# Supply_3V3.net
KiCad netlist of a schematic drawn in Altium Designer
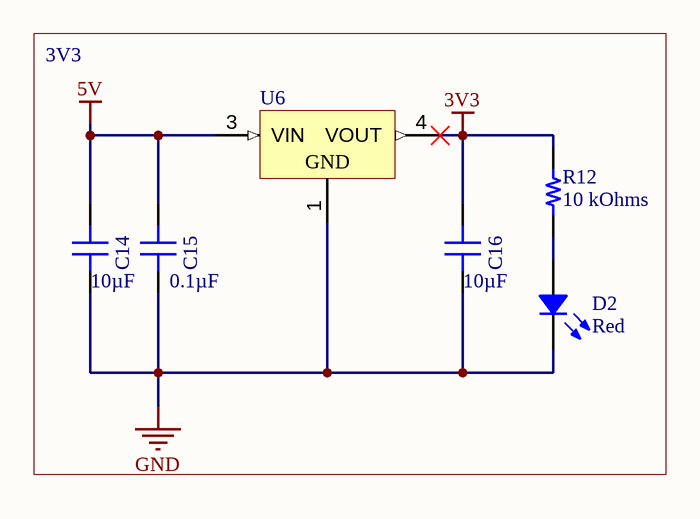
[diagram p0: Supply_3V3.SchDoc]

(export (version "E")
  (design (tool "Eeschema 10.0.6"))
  (components
    (comp (ref "C14")
      (value "10µF")
      (footprint "CAP 0805_2012")
      (description "CAP CER 10UF 16V X5R 0805")
      (fields (field (name "TOLERANCE") "±10%") (field (name "PART NUMBER") "0805YD106KAT2A"))
      (libsource (lib "Celestial Altium Library - altium_library") (part "Capacitor"))
    )
    (comp (ref "C15")
      (value "~")
      (footprint "CAP 0805_2012")
      (description "CAP CER 0.1UF 25V Z5U 0805")
      (fields
        (field (name "TOLERANCE") "-20%, +80%")
        (field (name "PART NUMBER") "08053E104ZAT2A")
        (field (name "CAPACITANCE") "0.1µF")
      )
      (libsource (lib "Celestial Altium Library - altium_library") (part "Capacitor"))
    )
    (comp (ref "C16")
      (value "10µF")
      (footprint "CAP 0805_2012")
      (description "CAP CER 10UF 16V X5R 0805")
      (fields (field (name "TOLERANCE") "±10%") (field (name "PART NUMBER") "0805YD106KAT2A"))
      (libsource (lib "Celestial Altium Library - altium_library") (part "Capacitor"))
    )
    (comp (ref "D2")
      (value "Red")
      (footprint "LED 0603_1608 RED")
      (description "LED RED CLEAR 0603 SMD")
      (fields
        (field (name "PART NUMBER") "LR Q976.01-P2R2-1")
        (field (name "MANUFACTURER") "ams-OSRAM USA Inc.")
      )
      (libsource (lib "Celestial Altium Library - altium_library") (part "LED"))
    )
    (comp (ref "R12")
      (value "10 kOhms")
      (footprint "YAGEO RES 0603_1608")
      (description "RES SMD 10K OHM 5% 1/10W 0603")
      (fields (field (name "PART NUMBER") "AC0603JR-0710KL") (field (name "MANUFACTURER") "Yageo"))
      (libsource (lib "Celestial Altium Library - altium_library") (part "Resistor"))
    )
    (comp (ref "U6")
      (value "~")
      (footprint "DPAK456P1010X240-3N")
      (description "Linear Voltage Regulator IC 1 Output 800mA DPAK")
      (fields (field (name "MP") "LD1117DT33TR") (field (name "MF") "STMicroelectronics"))
      (libsource (lib "CPAP_POWER") (part "LD1117DT33TR"))
    )
  )
  (nets
    (net (code "1") (name "3V3") (class "Default")
      (node (ref "C16") (pin "1") (pinfunction "1_1") (pintype "passive"))
      (node (ref "R12") (pin "2") (pinfunction "2_2") (pintype "passive"))
      (node (ref "U6") (pin "4") (pinfunction "VOUT_4") (pintype "output"))
    )
    (net (code "2") (name "5V") (class "Default")
      (node (ref "C14") (pin "1") (pinfunction "1_1") (pintype "passive"))
      (node (ref "C15") (pin "1") (pinfunction "1_1") (pintype "passive"))
      (node (ref "U6") (pin "3") (pinfunction "VIN_3") (pintype "input"))
    )
    (net (code "3") (name "GND") (class "Default")
      (node (ref "C14") (pin "2") (pinfunction "2_2") (pintype "passive"))
      (node (ref "C15") (pin "2") (pinfunction "2_2") (pintype "passive"))
      (node (ref "C16") (pin "2") (pinfunction "2_2") (pintype "passive"))
      (node (ref "D2") (pin "2") (pinfunction "2_2") (pintype "passive"))
      (node (ref "U6") (pin "1") (pinfunction "GND_1") (pintype "power_in"))
    )
    (net (code "4") (name "Net-(D2-Pad1)") (class "Default")
      (node (ref "D2") (pin "1") (pinfunction "1_1") (pintype "passive"))
      (node (ref "R12") (pin "1") (pinfunction "1_1") (pintype "passive"))
    )
  )
)
